# Microphones.net
KiCad netlist of a schematic drawn in Altium Designer
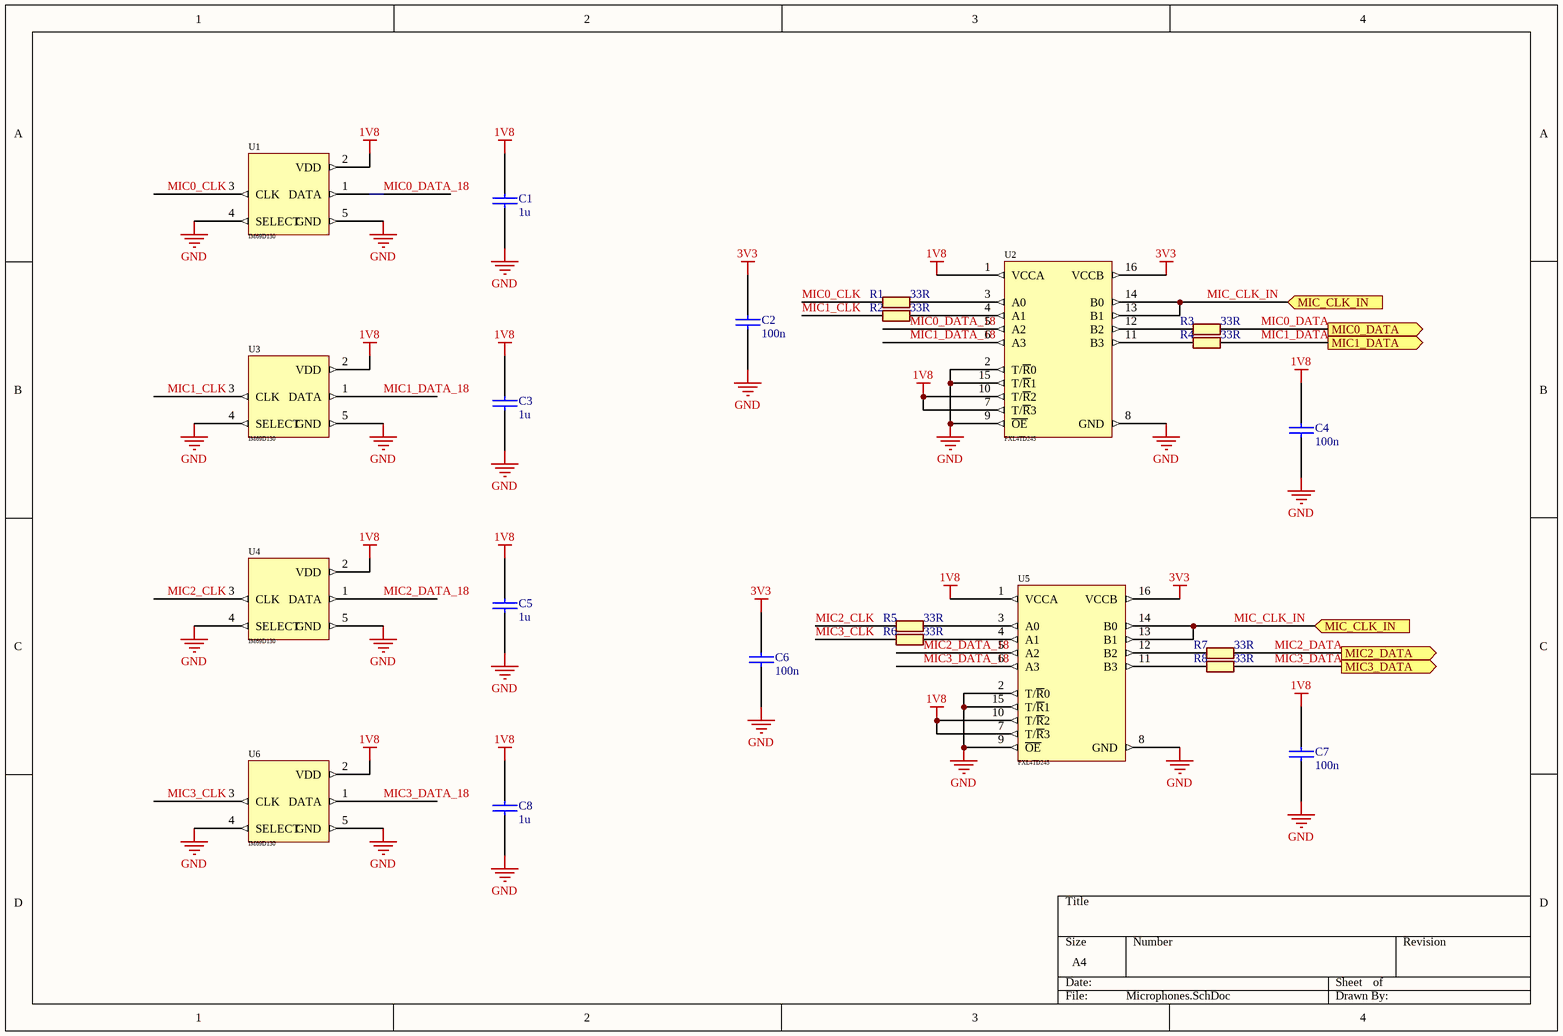
[diagram p0: Microphones.SchDoc]

(export (version "E")
  (design (tool "Eeschema 10.0.6"))
  (components
    (comp (ref "C1")
      (value "1u")
      (footprint "C0603")
      (description "Capacitor")
      (libsource (lib "Library") (part "CAP"))
    )
    (comp (ref "C2")
      (value "100n")
      (footprint "C0603")
      (description "Capacitor")
      (libsource (lib "Library") (part "CAP"))
    )
    (comp (ref "C3")
      (value "1u")
      (footprint "C0603")
      (description "Capacitor")
      (libsource (lib "Library") (part "CAP"))
    )
    (comp (ref "C4")
      (value "100n")
      (footprint "C0603")
      (description "Capacitor")
      (libsource (lib "Library") (part "CAP"))
    )
    (comp (ref "C5")
      (value "1u")
      (footprint "C0603")
      (description "Capacitor")
      (libsource (lib "Library") (part "CAP"))
    )
    (comp (ref "C6")
      (value "100n")
      (footprint "C0603")
      (description "Capacitor")
      (libsource (lib "Library") (part "CAP"))
    )
    (comp (ref "C7")
      (value "100n")
      (footprint "C0603")
      (description "Capacitor")
      (libsource (lib "Library") (part "CAP"))
    )
    (comp (ref "C8")
      (value "1u")
      (footprint "C0603")
      (description "Capacitor")
      (libsource (lib "Library") (part "CAP"))
    )
    (comp (ref "R1")
      (value "33R")
      (footprint "R0603")
      (description "RES")
      (libsource (lib "Library") (part "R"))
    )
    (comp (ref "R2")
      (value "33R")
      (footprint "R0603")
      (description "RES")
      (libsource (lib "Library") (part "R"))
    )
    (comp (ref "R3")
      (value "33R")
      (footprint "R0603")
      (description "RES")
      (libsource (lib "Library") (part "R"))
    )
    (comp (ref "R4")
      (value "33R")
      (footprint "R0603")
      (description "RES")
      (libsource (lib "Library") (part "R"))
    )
    (comp (ref "R5")
      (value "33R")
      (footprint "R0603")
      (description "RES")
      (libsource (lib "Library") (part "R"))
    )
    (comp (ref "R6")
      (value "33R")
      (footprint "R0603")
      (description "RES")
      (libsource (lib "Library") (part "R"))
    )
    (comp (ref "R7")
      (value "33R")
      (footprint "R0603")
      (description "RES")
      (libsource (lib "Library") (part "R"))
    )
    (comp (ref "R8")
      (value "33R")
      (footprint "R0603")
      (description "RES")
      (libsource (lib "Library") (part "R"))
    )
    (comp (ref "U1")
      (value "IM69D130")
      (footprint "IM69D130 - duplicate")
      (libsource (lib "Library") (part "IM69D130"))
    )
    (comp (ref "U2") (value "FXL4TD245") (footprint "DQFN16") (libsource (lib "Library") (part "FXL4TD245")))
    (comp (ref "U3")
      (value "IM69D130")
      (footprint "IM69D130 - duplicate")
      (libsource (lib "Library") (part "IM69D130"))
    )
    (comp (ref "U4")
      (value "IM69D130")
      (footprint "IM69D130 - duplicate")
      (libsource (lib "Library") (part "IM69D130"))
    )
    (comp (ref "U5") (value "FXL4TD245") (footprint "DQFN16") (libsource (lib "Library") (part "FXL4TD245")))
    (comp (ref "U6")
      (value "IM69D130")
      (footprint "IM69D130 - duplicate")
      (libsource (lib "Library") (part "IM69D130"))
    )
  )
  (nets
    (net (code "1") (name "/MIC0_CLK") (class "Default")
      (node (ref "R1") (pin "1") (pinfunction "1_1") (pintype "passive"))
      (node (ref "U1") (pin "3") (pinfunction "CLK_3") (pintype "output"))
    )
    (net (code "2") (name "/MIC0_DATA") (class "Default")
      (node (ref "R3") (pin "2") (pinfunction "2_2") (pintype "passive"))
    )
    (net (code "3") (name "/MIC0_DATA_18") (class "Default")
      (node (ref "U1") (pin "1") (pinfunction "DATA_1") (pintype "output"))
      (node (ref "U2") (pin "5") (pinfunction "A2_5") (pintype "output"))
    )
    (net (code "4") (name "/MIC1_CLK") (class "Default")
      (node (ref "R2") (pin "1") (pinfunction "1_1") (pintype "passive"))
      (node (ref "U3") (pin "3") (pinfunction "CLK_3") (pintype "output"))
    )
    (net (code "5") (name "/MIC1_DATA") (class "Default")
      (node (ref "R4") (pin "2") (pinfunction "2_2") (pintype "passive"))
    )
    (net (code "6") (name "/MIC1_DATA_18") (class "Default")
      (node (ref "U2") (pin "6") (pinfunction "A3_6") (pintype "output"))
      (node (ref "U3") (pin "1") (pinfunction "DATA_1") (pintype "output"))
    )
    (net (code "7") (name "/MIC2_CLK") (class "Default")
      (node (ref "R5") (pin "1") (pinfunction "1_1") (pintype "passive"))
      (node (ref "U4") (pin "3") (pinfunction "CLK_3") (pintype "output"))
    )
    (net (code "8") (name "/MIC2_DATA") (class "Default")
      (node (ref "R7") (pin "2") (pinfunction "2_2") (pintype "passive"))
    )
    (net (code "9") (name "/MIC2_DATA_18") (class "Default")
      (node (ref "U4") (pin "1") (pinfunction "DATA_1") (pintype "output"))
      (node (ref "U5") (pin "5") (pinfunction "A2_5") (pintype "output"))
    )
    (net (code "10") (name "/MIC3_CLK") (class "Default")
      (node (ref "R6") (pin "1") (pinfunction "1_1") (pintype "passive"))
      (node (ref "U6") (pin "3") (pinfunction "CLK_3") (pintype "output"))
    )
    (net (code "11") (name "/MIC3_DATA") (class "Default")
      (node (ref "R8") (pin "2") (pinfunction "2_2") (pintype "passive"))
    )
    (net (code "12") (name "/MIC3_DATA_18") (class "Default")
      (node (ref "U5") (pin "6") (pinfunction "A3_6") (pintype "output"))
      (node (ref "U6") (pin "1") (pinfunction "DATA_1") (pintype "output"))
    )
    (net (code "13") (name "/MIC_CLK_IN") (class "Default")
      (node (ref "U2") (pin "13") (pinfunction "B1_13") (pintype "output"))
      (node (ref "U2") (pin "14") (pinfunction "B0_14") (pintype "output"))
      (node (ref "U5") (pin "13") (pinfunction "B1_13") (pintype "output"))
      (node (ref "U5") (pin "14") (pinfunction "B0_14") (pintype "output"))
    )
    (net (code "14") (name "1V8") (class "Default")
      (node (ref "C1") (pin "1") (pinfunction "1_1") (pintype "passive"))
      (node (ref "C3") (pin "1") (pinfunction "1_1") (pintype "passive"))
      (node (ref "C4") (pin "1") (pinfunction "1_1") (pintype "passive"))
      (node (ref "C5") (pin "1") (pinfunction "1_1") (pintype "passive"))
      (node (ref "C7") (pin "1") (pinfunction "1_1") (pintype "passive"))
      (node (ref "C8") (pin "1") (pinfunction "1_1") (pintype "passive"))
      (node (ref "U1") (pin "2") (pinfunction "VDD_2") (pintype "output"))
      (node (ref "U2") (pin "1") (pinfunction "VCCA_1") (pintype "output"))
      (node (ref "U2") (pin "10") (pinfunction "T/~{R}2_10") (pintype "output"))
      (node (ref "U2") (pin "7") (pinfunction "T/~{R}3_7") (pintype "output"))
      (node (ref "U3") (pin "2") (pinfunction "VDD_2") (pintype "output"))
      (node (ref "U4") (pin "2") (pinfunction "VDD_2") (pintype "output"))
      (node (ref "U5") (pin "1") (pinfunction "VCCA_1") (pintype "output"))
      (node (ref "U5") (pin "10") (pinfunction "T/~{R}2_10") (pintype "output"))
      (node (ref "U5") (pin "7") (pinfunction "T/~{R}3_7") (pintype "output"))
      (node (ref "U6") (pin "2") (pinfunction "VDD_2") (pintype "output"))
    )
    (net (code "15") (name "3V3") (class "Default")
      (node (ref "C2") (pin "1") (pinfunction "1_1") (pintype "passive"))
      (node (ref "C6") (pin "1") (pinfunction "1_1") (pintype "passive"))
      (node (ref "U2") (pin "16") (pinfunction "VCCB_16") (pintype "output"))
      (node (ref "U5") (pin "16") (pinfunction "VCCB_16") (pintype "output"))
    )
    (net (code "16") (name "GND") (class "Default")
      (node (ref "C1") (pin "2") (pinfunction "2_2") (pintype "passive"))
      (node (ref "C2") (pin "2") (pinfunction "2_2") (pintype "passive"))
      (node (ref "C3") (pin "2") (pinfunction "2_2") (pintype "passive"))
      (node (ref "C4") (pin "2") (pinfunction "2_2") (pintype "passive"))
      (node (ref "C5") (pin "2") (pinfunction "2_2") (pintype "passive"))
      (node (ref "C6") (pin "2") (pinfunction "2_2") (pintype "passive"))
      (node (ref "C7") (pin "2") (pinfunction "2_2") (pintype "passive"))
      (node (ref "C8") (pin "2") (pinfunction "2_2") (pintype "passive"))
      (node (ref "U1") (pin "4") (pinfunction "SELECT_4") (pintype "output"))
      (node (ref "U1") (pin "5") (pinfunction "GND_5") (pintype "output"))
      (node (ref "U2") (pin "15") (pinfunction "T/~{R}1_15") (pintype "output"))
      (node (ref "U2") (pin "2") (pinfunction "T/~{R}0_2") (pintype "output"))
      (node (ref "U2") (pin "8") (pinfunction "GND_8") (pintype "output"))
      (node (ref "U2") (pin "9") (pinfunction "~{OE}_9") (pintype "output"))
      (node (ref "U3") (pin "4") (pinfunction "SELECT_4") (pintype "output"))
      (node (ref "U3") (pin "5") (pinfunction "GND_5") (pintype "output"))
      (node (ref "U4") (pin "4") (pinfunction "SELECT_4") (pintype "output"))
      (node (ref "U4") (pin "5") (pinfunction "GND_5") (pintype "output"))
      (node (ref "U5") (pin "15") (pinfunction "T/~{R}1_15") (pintype "output"))
      (node (ref "U5") (pin "2") (pinfunction "T/~{R}0_2") (pintype "output"))
      (node (ref "U5") (pin "8") (pinfunction "GND_8") (pintype "output"))
      (node (ref "U5") (pin "9") (pinfunction "~{OE}_9") (pintype "output"))
      (node (ref "U6") (pin "4") (pinfunction "SELECT_4") (pintype "output"))
      (node (ref "U6") (pin "5") (pinfunction "GND_5") (pintype "output"))
    )
    (net (code "17") (name "Net-(U2-A0)") (class "Default")
      (node (ref "R1") (pin "2") (pinfunction "2_2") (pintype "passive"))
      (node (ref "U2") (pin "3") (pinfunction "A0_3") (pintype "output"))
    )
    (net (code "18") (name "Net-(U2-A1)") (class "Default")
      (node (ref "R2") (pin "2") (pinfunction "2_2") (pintype "passive"))
      (node (ref "U2") (pin "4") (pinfunction "A1_4") (pintype "output"))
    )
    (net (code "19") (name "Net-(U2-B2)") (class "Default")
      (node (ref "R3") (pin "1") (pinfunction "1_1") (pintype "passive"))
      (node (ref "U2") (pin "12") (pinfunction "B2_12") (pintype "output"))
    )
    (net (code "20") (name "Net-(U2-B3)") (class "Default")
      (node (ref "R4") (pin "1") (pinfunction "1_1") (pintype "passive"))
      (node (ref "U2") (pin "11") (pinfunction "B3_11") (pintype "output"))
    )
    (net (code "21") (name "Net-(U5-A0)") (class "Default")
      (node (ref "R5") (pin "2") (pinfunction "2_2") (pintype "passive"))
      (node (ref "U5") (pin "3") (pinfunction "A0_3") (pintype "output"))
    )
    (net (code "22") (name "Net-(U5-A1)") (class "Default")
      (node (ref "R6") (pin "2") (pinfunction "2_2") (pintype "passive"))
      (node (ref "U5") (pin "4") (pinfunction "A1_4") (pintype "output"))
    )
    (net (code "23") (name "Net-(U5-B2)") (class "Default")
      (node (ref "R7") (pin "1") (pinfunction "1_1") (pintype "passive"))
      (node (ref "U5") (pin "12") (pinfunction "B2_12") (pintype "output"))
    )
    (net (code "24") (name "Net-(U5-B3)") (class "Default")
      (node (ref "R8") (pin "1") (pinfunction "1_1") (pintype "passive"))
      (node (ref "U5") (pin "11") (pinfunction "B3_11") (pintype "output"))
    )
  )
)
